# RS232_RS485.net
KiCad netlist of a schematic drawn in Altium Designer
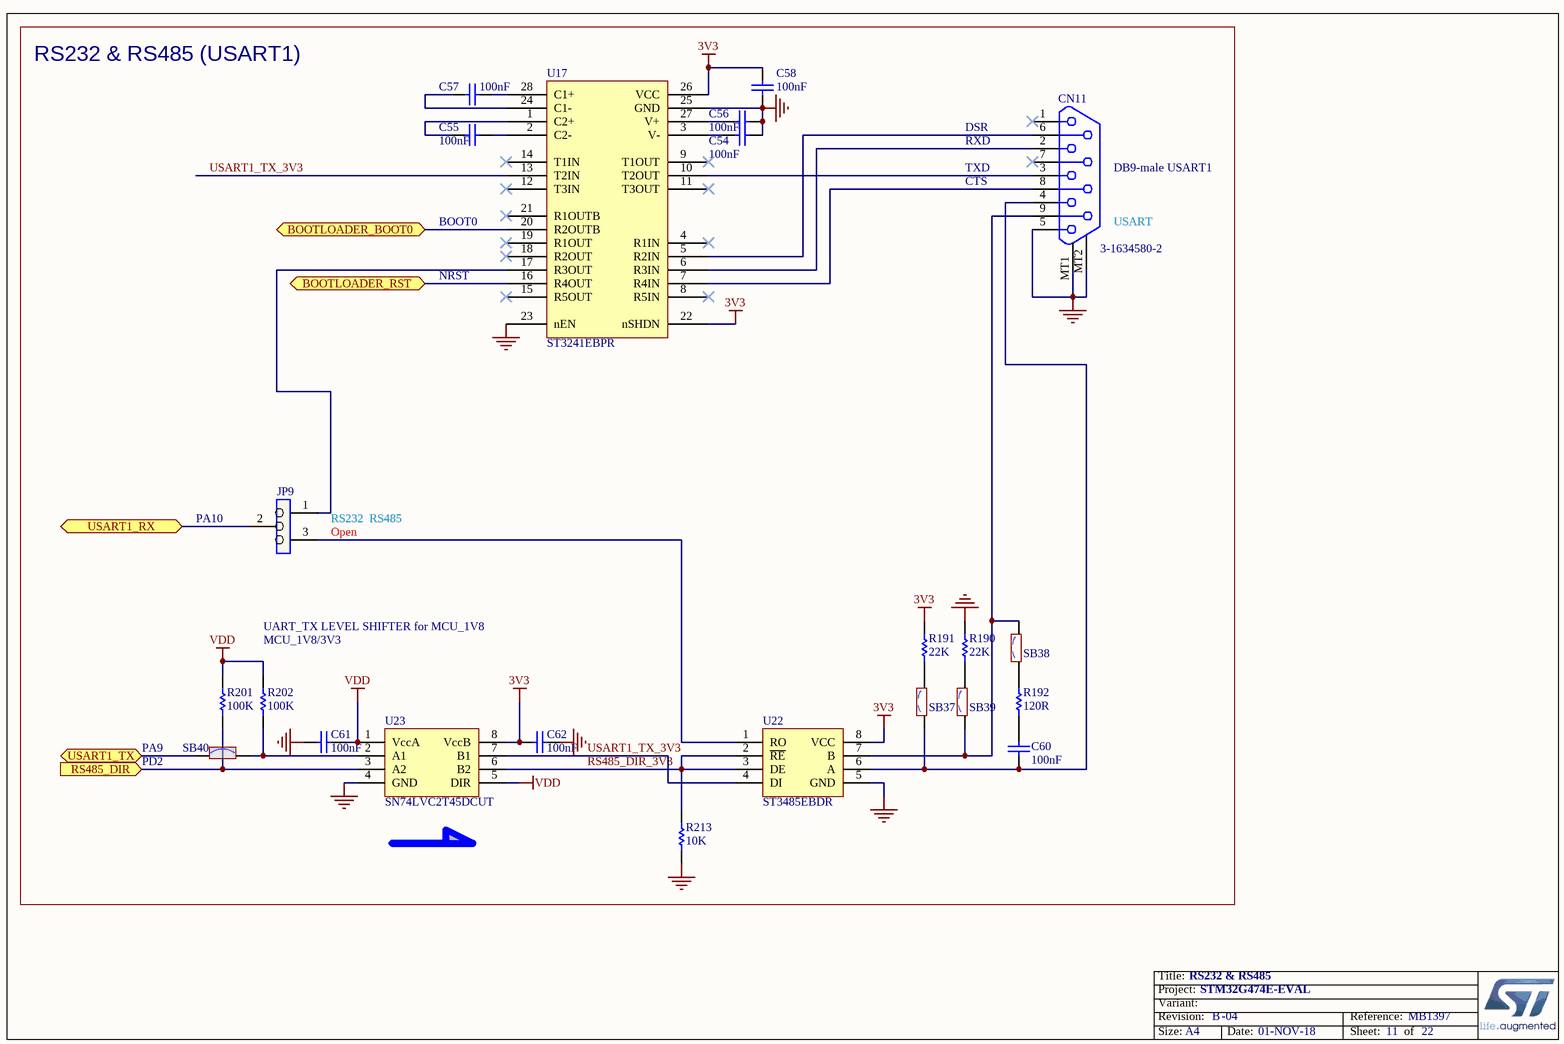
[diagram p0: RS232&RS485.SchDoc]

(export (version "E")
  (design (tool "Eeschema 10.0.6"))
  (components
    (comp (ref "C54")
      (value "100nF")
      (footprint "C0402")
      (description "Capacitor, MLCC, 100nF, 16V, X7R, 10%, 0402, T=0.5mm")
      (fields
        (field (name "INTERNAL_PART_NUMBER") "MCD-00006")
        (field (name "MANUFACTURER_PART_NUMBER") "CC0402KRX7R7BB104")
        (field (name "PROVIDED_BY") "SUBCO")
      )
      (libsource (lib "MCD_PARTS_database") (part "Capacitor"))
    )
    (comp (ref "C55")
      (value "100nF")
      (footprint "C0402")
      (description "Capacitor, MLCC, 100nF, 16V, X7R, 10%, 0402, T=0.5mm")
      (fields
        (field (name "INTERNAL_PART_NUMBER") "MCD-00006")
        (field (name "MANUFACTURER_PART_NUMBER") "CC0402KRX7R7BB104")
        (field (name "PROVIDED_BY") "SUBCO")
      )
      (libsource (lib "MCD_PARTS_database") (part "Capacitor"))
    )
    (comp (ref "C56")
      (value "100nF")
      (footprint "C0402")
      (description "Capacitor, MLCC, 100nF, 16V, X7R, 10%, 0402, T=0.5mm")
      (fields
        (field (name "INTERNAL_PART_NUMBER") "MCD-00006")
        (field (name "MANUFACTURER_PART_NUMBER") "CC0402KRX7R7BB104")
        (field (name "PROVIDED_BY") "SUBCO")
      )
      (libsource (lib "MCD_PARTS_database") (part "Capacitor"))
    )
    (comp (ref "C57")
      (value "100nF")
      (footprint "C0402")
      (description "Capacitor, MLCC, 100nF, 16V, X7R, 10%, 0402, T=0.5mm")
      (fields
        (field (name "INTERNAL_PART_NUMBER") "MCD-00006")
        (field (name "MANUFACTURER_PART_NUMBER") "CC0402KRX7R7BB104")
        (field (name "PROVIDED_BY") "SUBCO")
      )
      (libsource (lib "MCD_PARTS_database") (part "Capacitor"))
    )
    (comp (ref "C58")
      (value "100nF")
      (footprint "C0402")
      (description "Capacitor, MLCC, 100nF, 16V, X7R, 10%, 0402, T=0.5mm")
      (fields
        (field (name "INTERNAL_PART_NUMBER") "MCD-00006")
        (field (name "MANUFACTURER_PART_NUMBER") "CC0402KRX7R7BB104")
        (field (name "PROVIDED_BY") "SUBCO")
      )
      (libsource (lib "MCD_PARTS_database") (part "Capacitor"))
    )
    (comp (ref "C60")
      (value "100nF")
      (footprint "C0603")
      (description "Capacitor, MLCC, 100nF, 16V, X7R, 10%, 0603, T=0,8mm")
      (fields
        (field (name "INTERNAL_PART_NUMBER") "MCD-00211")
        (field (name "MANUFACTURER_PART_NUMBER") "CC0603KRX7R7BB104")
        (field (name "PROVIDED_BY") "SUBCO")
      )
      (libsource (lib "MCD_PARTS_database") (part "Capacitor"))
    )
    (comp (ref "C61")
      (value "100nF")
      (footprint "C0603")
      (description "Capacitor, MLCC, 100nF, 16V, X7R, 10%, 0603, T=0,8mm")
      (fields
        (field (name "INTERNAL_PART_NUMBER") "MCD-00211")
        (field (name "MANUFACTURER_PART_NUMBER") "CC0603KRX7R7BB104")
        (field (name "PROVIDED_BY") "SUBCO")
      )
      (libsource (lib "MCD_PARTS_database") (part "Capacitor"))
    )
    (comp (ref "C62")
      (value "100nF")
      (footprint "C0603")
      (description "Capacitor, MLCC, 100nF, 16V, X7R, 10%, 0603, T=0,8mm")
      (fields
        (field (name "INTERNAL_PART_NUMBER") "MCD-00211")
        (field (name "MANUFACTURER_PART_NUMBER") "CC0603KRX7R7BB104")
        (field (name "PROVIDED_BY") "SUBCO")
      )
      (libsource (lib "MCD_PARTS_database") (part "Capacitor"))
    )
    (comp (ref "CN11")
      (value "3-1634580-2")
      (footprint "CON_DB9-MALE_TYCO_3-1634580-2")
      (description "Header, DB9, RA, TH, Height 13.57mm")
      (fields
        (field (name "INTERNAL_PART_NUMBER") "MCD-00127")
        (field (name "MANUFACTURER") "TYCO")
        (field (name "PROVIDED_BY") "SUBCO")
      )
      (libsource (lib "MCD_PARTS_database") (part "DB9_Header_male_3-1634580-2"))
    )
    (comp (ref "JP9")
      (value "Jumper_Header 3x1")
      (footprint "CON_SAMTEC_TSW-103-07-F-S")
      (description "Header, 3x1, 2,54mm, VR, TH, Height 5.84mm/2.54mm")
      (fields
        (field (name "INTERNAL_PART_NUMBER") "MCD-00111")
        (field (name "MANUFACTURER_PART_NUMBER") "TSW-103-07-F-S")
        (field (name "PROVIDED_BY") "SUBCO")
      )
      (libsource (lib "MCD_PARTS_database") (part "Jumper_Header 3x1"))
    )
    (comp (ref "R190")
      (value "22K")
      (footprint "R0603")
      (description "Resistor,22K,0603,1%,1/10W")
      (fields
        (field (name "INTERNAL_PART_NUMBER") "MCD-00430")
        (field (name "MANUFACTURER_PART_NUMBER") "RC0603FR-0722KL")
        (field (name "PROVIDED_BY") "SUBCO")
      )
      (libsource (lib "MCD_PARTS_database") (part "Resistor"))
    )
    (comp (ref "R191")
      (value "22K")
      (footprint "R0603")
      (description "Resistor,22K,0603,1%,1/10W")
      (fields
        (field (name "INTERNAL_PART_NUMBER") "MCD-00430")
        (field (name "MANUFACTURER_PART_NUMBER") "RC0603FR-0722KL")
        (field (name "PROVIDED_BY") "SUBCO")
      )
      (libsource (lib "MCD_PARTS_database") (part "Resistor"))
    )
    (comp (ref "R192")
      (value "120R")
      (footprint "R0603")
      (description "Resistor,120R,0603,1%,1/10W")
      (fields
        (field (name "INTERNAL_PART_NUMBER") "MCD-00338")
        (field (name "MANUFACTURER_PART_NUMBER") "RC0603FR-07120RL")
        (field (name "PROVIDED_BY") "SUBCO")
      )
      (libsource (lib "MCD_PARTS_database") (part "Resistor"))
    )
    (comp (ref "R201")
      (value "100K")
      (footprint "R0603")
      (description "Resistor,100K,0603,1%,1/10W")
      (fields
        (field (name "INTERNAL_PART_NUMBER") "MCD-00223")
        (field (name "MANUFACTURER_PART_NUMBER") "RC0603FR-07100KL")
        (field (name "PROVIDED_BY") "SUBCO")
      )
      (libsource (lib "MCD_PARTS_database") (part "Resistor"))
    )
    (comp (ref "R202")
      (value "100K")
      (footprint "R0603")
      (description "Resistor,100K,0603,1%,1/10W")
      (fields
        (field (name "INTERNAL_PART_NUMBER") "MCD-00223")
        (field (name "MANUFACTURER_PART_NUMBER") "RC0603FR-07100KL")
        (field (name "PROVIDED_BY") "SUBCO")
      )
      (libsource (lib "MCD_PARTS_database") (part "Resistor"))
    )
    (comp (ref "R213")
      (value "10K")
      (footprint "R0603")
      (description "Resistor,10K,0603,1%,1/10W")
      (fields
        (field (name "INTERNAL_PART_NUMBER") "MCD-00220")
        (field (name "MANUFACTURER_PART_NUMBER") "RC0603FR-0710KL")
        (field (name "PROVIDED_BY") "SUBCO")
      )
      (libsource (lib "MCD_PARTS_database") (part "Resistor"))
    )
    (comp (ref "SB37")
      (value "SB_OFF")
      (footprint "SOLDER-BRIDGE_R0603-0R")
      (description "Solder Bridge OFF")
      (fields
        (field (name "INTERNAL_PART_NUMBER") "MCD-00072")
        (field (name "MANUFACTURER_PART_NUMBER") "RC0603JR-070RL")
        (field (name "PROVIDED_BY") "SUBCO")
      )
      (libsource (lib "MCD_PARTS_database") (part "SB_OFF"))
    )
    (comp (ref "SB38")
      (value "SB_OFF")
      (footprint "SOLDER-BRIDGE_R0603-0R")
      (description "Solder Bridge OFF")
      (fields
        (field (name "INTERNAL_PART_NUMBER") "MCD-00072")
        (field (name "MANUFACTURER_PART_NUMBER") "RC0603JR-070RL")
        (field (name "PROVIDED_BY") "SUBCO")
      )
      (libsource (lib "MCD_PARTS_database") (part "SB_OFF"))
    )
    (comp (ref "SB39")
      (value "SB_OFF")
      (footprint "SOLDER-BRIDGE_R0603-0R")
      (description "Solder Bridge OFF")
      (fields
        (field (name "INTERNAL_PART_NUMBER") "MCD-00072")
        (field (name "MANUFACTURER_PART_NUMBER") "RC0603JR-070RL")
        (field (name "PROVIDED_BY") "SUBCO")
      )
      (libsource (lib "MCD_PARTS_database") (part "SB_OFF"))
    )
    (comp (ref "SB40")
      (value "SB_ON")
      (footprint "SOLDER-BRIDGE_R0603-0R")
      (description "Solder Bridge ON")
      (fields
        (field (name "INTERNAL_PART_NUMBER") "MCD-00071")
        (field (name "MANUFACTURER_PART_NUMBER") "RC0603JR-070RL")
        (field (name "PROVIDED_BY") "SUBCO")
      )
      (libsource (lib "MCD_PARTS_database") (part "SB_ON"))
    )
    (comp (ref "U17")
      (value "ST3241EBPR")
      (footprint "ICC_SSOP28_10P2X5P3_P065")
      (description "RS-232 transceiver with auto-power-down")
      (fields
        (field (name "INTERNAL_PART_NUMBER") "MCD-00152")
        (field (name "MANUFACTURER") "STMICROELECTRONICS")
        (field (name "PROVIDED_BY") "SUBCO with ST control")
      )
      (libsource (lib "MCD_PARTS_database") (part "ST3241EBPR"))
    )
    (comp (ref "U22")
      (value "ST3485EBDR")
      (footprint "ICC_SO8_5X4_P127")
      (description "RS-485/RS-422 transceiver Up to 12Mbps")
      (fields
        (field (name "INTERNAL_PART_NUMBER") "MCD-01160")
        (field (name "MANUFACTURER") "STMICROELECTRONICS")
        (field (name "PROVIDED_BY") "SUBCO with ST control")
      )
      (libsource (lib "MCD_PARTS_database") (part "ST3485EBDR"))
    )
    (comp (ref "U23")
      (value "SN74LVC2T45DCUT")
      (footprint "ICC_VSSOP8_DCU_R-PDSO-G8_2X2P30_P050")
      (description "Dual bit dual supply bus transceiver")
      (fields
        (field (name "INTERNAL_PART_NUMBER") "MCD-00264")
        (field (name "MANUFACTURER") "TEXAS INSTRUMENTS")
        (field (name "PROVIDED_BY") "SUBCO")
      )
      (libsource (lib "MCD_PARTS_database") (part "SN74LVC2T45DCUT"))
    )
  )
  (nets
    (net (code "1") (name "/BOOTLOADER_BOOT0") (class "Default")
      (node (ref "U17") (pin "20") (pinfunction "R2OUTB_20") (pintype "passive"))
    )
    (net (code "2") (name "/BOOTLOADER_RST") (class "Default")
      (node (ref "U17") (pin "16") (pinfunction "R4OUT_16") (pintype "passive"))
    )
    (net (code "3") (name "/RS485_DIR") (class "Default")
      (node (ref "R201") (pin "1") (pinfunction "1_1") (pintype "passive"))
      (node (ref "U23") (pin "3") (pinfunction "A2_3") (pintype "passive"))
    )
    (net (code "4") (name "/RS485_DIR_3V3") (class "Default")
      (node (ref "R213") (pin "2") (pinfunction "2_2") (pintype "passive"))
      (node (ref "U22") (pin "2") (pinfunction "~{RE}_2") (pintype "passive"))
      (node (ref "U22") (pin "3") (pinfunction "DE_3") (pintype "passive"))
      (node (ref "U23") (pin "6") (pinfunction "B2_6") (pintype "passive"))
    )
    (net (code "5") (name "/USART1_RX") (class "Default")
      (node (ref "JP9") (pin "2") (pinfunction "2_2") (pintype "passive"))
    )
    (net (code "6") (name "/USART1_TX") (class "Default")
      (node (ref "SB40") (pin "1") (pinfunction "1_1") (pintype "passive"))
    )
    (net (code "7") (name "/USART1_TX_3V3") (class "Default")
      (node (ref "U17") (pin "13") (pinfunction "T2IN_13") (pintype "passive"))
      (node (ref "U22") (pin "4") (pinfunction "DI_4") (pintype "passive"))
      (node (ref "U23") (pin "7") (pinfunction "B1_7") (pintype "passive"))
    )
    (net (code "8") (name "3V3") (class "Default")
      (node (ref "C58") (pin "1") (pinfunction "1_1") (pintype "passive"))
      (node (ref "C62") (pin "2") (pinfunction "2_2") (pintype "passive"))
      (node (ref "R191") (pin "1") (pinfunction "1_1") (pintype "passive"))
      (node (ref "U17") (pin "22") (pinfunction "nSHDN_22") (pintype "passive"))
      (node (ref "U17") (pin "26") (pinfunction "VCC_26") (pintype "passive"))
      (node (ref "U22") (pin "8") (pinfunction "VCC_8") (pintype "passive"))
      (node (ref "U23") (pin "8") (pinfunction "VccB_8") (pintype "power_in"))
    )
    (net (code "9") (name "GND") (class "Default")
      (node (ref "C54") (pin "1") (pinfunction "1_1") (pintype "passive"))
      (node (ref "C56") (pin "1") (pinfunction "1_1") (pintype "passive"))
      (node (ref "C58") (pin "2") (pinfunction "2_2") (pintype "passive"))
      (node (ref "C61") (pin "2") (pinfunction "2_2") (pintype "passive"))
      (node (ref "C62") (pin "1") (pinfunction "1_1") (pintype "passive"))
      (node (ref "CN11") (pin "5") (pintype "passive"))
      (node (ref "CN11") (pin "MT1") (pintype "passive"))
      (node (ref "CN11") (pin "MT2") (pintype "passive"))
      (node (ref "R190") (pin "2") (pinfunction "2_2") (pintype "passive"))
      (node (ref "R213") (pin "1") (pinfunction "1_1") (pintype "passive"))
      (node (ref "U17") (pin "23") (pinfunction "nEN_23") (pintype "passive"))
      (node (ref "U17") (pin "25") (pinfunction "GND_25") (pintype "passive"))
      (node (ref "U22") (pin "5") (pinfunction "GND_5") (pintype "passive"))
      (node (ref "U23") (pin "4") (pinfunction "GND_4") (pintype "power_in"))
    )
    (net (code "10") (name "Net-(C60-Pad2)") (class "Default")
      (node (ref "C60") (pin "2") (pinfunction "2_2") (pintype "passive"))
      (node (ref "R192") (pin "1") (pinfunction "1_1") (pintype "passive"))
    )
    (net (code "11") (name "Net-(R190-Pad1)") (class "Default")
      (node (ref "R190") (pin "1") (pinfunction "1_1") (pintype "passive"))
      (node (ref "SB39") (pin "2") (pinfunction "2_2") (pintype "passive"))
    )
    (net (code "12") (name "Net-(R191-Pad2)") (class "Default")
      (node (ref "R191") (pin "2") (pinfunction "2_2") (pintype "passive"))
      (node (ref "SB37") (pin "2") (pinfunction "2_2") (pintype "passive"))
    )
    (net (code "13") (name "Net-(R192-Pad2)") (class "Default")
      (node (ref "R192") (pin "2") (pinfunction "2_2") (pintype "passive"))
      (node (ref "SB38") (pin "1") (pinfunction "1_1") (pintype "passive"))
    )
    (net (code "14") (name "Net-(U17-C1+)") (class "Default")
      (node (ref "C57") (pin "2") (pinfunction "2_2") (pintype "passive"))
      (node (ref "U17") (pin "28") (pinfunction "C1+_28") (pintype "passive"))
    )
    (net (code "15") (name "Net-(U17-C1-)") (class "Default")
      (node (ref "C57") (pin "1") (pinfunction "1_1") (pintype "passive"))
      (node (ref "U17") (pin "24") (pinfunction "C1-_24") (pintype "passive"))
    )
    (net (code "16") (name "Net-(U17-C2+)") (class "Default")
      (node (ref "C55") (pin "1") (pinfunction "1_1") (pintype "passive"))
      (node (ref "U17") (pin "1") (pinfunction "C2+_1") (pintype "passive"))
    )
    (net (code "17") (name "Net-(U17-C2-)") (class "Default")
      (node (ref "C55") (pin "2") (pinfunction "2_2") (pintype "passive"))
      (node (ref "U17") (pin "2") (pinfunction "C2-_2") (pintype "passive"))
    )
    (net (code "18") (name "Net-(U17-R2IN)") (class "Default")
      (node (ref "CN11") (pin "6") (pintype "passive"))
      (node (ref "U17") (pin "5") (pinfunction "R2IN_5") (pintype "passive"))
    )
    (net (code "19") (name "Net-(U17-R3IN)") (class "Default")
      (node (ref "CN11") (pin "2") (pintype "passive"))
      (node (ref "U17") (pin "6") (pinfunction "R3IN_6") (pintype "passive"))
    )
    (net (code "20") (name "Net-(U17-R3OUT)") (class "Default")
      (node (ref "JP9") (pin "1") (pinfunction "1_1") (pintype "passive"))
      (node (ref "U17") (pin "17") (pinfunction "R3OUT_17") (pintype "passive"))
    )
    (net (code "21") (name "Net-(U17-R4IN)") (class "Default")
      (node (ref "CN11") (pin "8") (pintype "passive"))
      (node (ref "U17") (pin "7") (pinfunction "R4IN_7") (pintype "passive"))
    )
    (net (code "22") (name "Net-(U17-T2OUT)") (class "Default")
      (node (ref "CN11") (pin "3") (pintype "passive"))
      (node (ref "U17") (pin "10") (pinfunction "T2OUT_10") (pintype "passive"))
    )
    (net (code "23") (name "Net-(U17-V+)") (class "Default")
      (node (ref "C56") (pin "2") (pinfunction "2_2") (pintype "passive"))
      (node (ref "U17") (pin "27") (pinfunction "V+_27") (pintype "passive"))
    )
    (net (code "24") (name "Net-(U17-V-)") (class "Default")
      (node (ref "C54") (pin "2") (pinfunction "2_2") (pintype "passive"))
      (node (ref "U17") (pin "3") (pinfunction "V-_3") (pintype "passive"))
    )
    (net (code "25") (name "Net-(U22-A)") (class "Default")
      (node (ref "C60") (pin "1") (pinfunction "1_1") (pintype "passive"))
      (node (ref "CN11") (pin "4") (pintype "passive"))
      (node (ref "SB37") (pin "1") (pinfunction "1_1") (pintype "passive"))
      (node (ref "U22") (pin "6") (pinfunction "A_6") (pintype "passive"))
    )
    (net (code "26") (name "Net-(U22-B)") (class "Default")
      (node (ref "CN11") (pin "9") (pintype "passive"))
      (node (ref "SB38") (pin "2") (pinfunction "2_2") (pintype "passive"))
      (node (ref "SB39") (pin "1") (pinfunction "1_1") (pintype "passive"))
      (node (ref "U22") (pin "7") (pinfunction "B_7") (pintype "passive"))
    )
    (net (code "27") (name "Net-(U22-RO)") (class "Default")
      (node (ref "JP9") (pin "3") (pinfunction "3_3") (pintype "passive"))
      (node (ref "U22") (pin "1") (pinfunction "RO_1") (pintype "passive"))
    )
    (net (code "28") (name "Net-(U23-A1)") (class "Default")
      (node (ref "R202") (pin "1") (pinfunction "1_1") (pintype "passive"))
      (node (ref "SB40") (pin "2") (pinfunction "2_2") (pintype "passive"))
      (node (ref "U23") (pin "2") (pinfunction "A1_2") (pintype "passive"))
    )
    (net (code "29") (name "VDD") (class "Default")
      (node (ref "C61") (pin "1") (pinfunction "1_1") (pintype "passive"))
      (node (ref "R201") (pin "2") (pinfunction "2_2") (pintype "passive"))
      (node (ref "R202") (pin "2") (pinfunction "2_2") (pintype "passive"))
      (node (ref "U23") (pin "1") (pinfunction "VccA_1") (pintype "power_in"))
      (node (ref "U23") (pin "5") (pinfunction "DIR_5") (pintype "passive"))
    )
    (net (code "30") (name "unconnected-(CN11-Pad1)") (class "Default")
      (node (ref "CN11") (pin "1") (pintype "passive+no_connect"))
    )
    (net (code "31") (name "unconnected-(CN11-Pad7)") (class "Default")
      (node (ref "CN11") (pin "7") (pintype "passive+no_connect"))
    )
    (net (code "32") (name "unconnected-(U17-R1IN-Pad4)") (class "Default")
      (node (ref "U17") (pin "4") (pinfunction "R1IN_4") (pintype "passive+no_connect"))
    )
    (net (code "33") (name "unconnected-(U17-R1OUT-Pad19)") (class "Default")
      (node (ref "U17") (pin "19") (pinfunction "R1OUT_19") (pintype "passive+no_connect"))
    )
    (net (code "34") (name "unconnected-(U17-R1OUTB-Pad21)") (class "Default")
      (node (ref "U17") (pin "21") (pinfunction "R1OUTB_21") (pintype "passive+no_connect"))
    )
    (net (code "35") (name "unconnected-(U17-R2OUT-Pad18)") (class "Default")
      (node (ref "U17") (pin "18") (pinfunction "R2OUT_18") (pintype "passive+no_connect"))
    )
    (net (code "36") (name "unconnected-(U17-R5IN-Pad8)") (class "Default")
      (node (ref "U17") (pin "8") (pinfunction "R5IN_8") (pintype "passive+no_connect"))
    )
    (net (code "37") (name "unconnected-(U17-R5OUT-Pad15)") (class "Default")
      (node (ref "U17") (pin "15") (pinfunction "R5OUT_15") (pintype "passive+no_connect"))
    )
    (net (code "38") (name "unconnected-(U17-T1IN-Pad14)") (class "Default")
      (node (ref "U17") (pin "14") (pinfunction "T1IN_14") (pintype "passive+no_connect"))
    )
    (net (code "39") (name "unconnected-(U17-T1OUT-Pad9)") (class "Default")
      (node (ref "U17") (pin "9") (pinfunction "T1OUT_9") (pintype "passive+no_connect"))
    )
    (net (code "40") (name "unconnected-(U17-T3IN-Pad12)") (class "Default")
      (node (ref "U17") (pin "12") (pinfunction "T3IN_12") (pintype "passive+no_connect"))
    )
    (net (code "41") (name "unconnected-(U17-T3OUT-Pad11)") (class "Default")
      (node (ref "U17") (pin "11") (pinfunction "T3OUT_11") (pintype "passive+no_connect"))
    )
  )
)
